# Encoders.net
KiCad netlist of a schematic drawn in Altium Designer
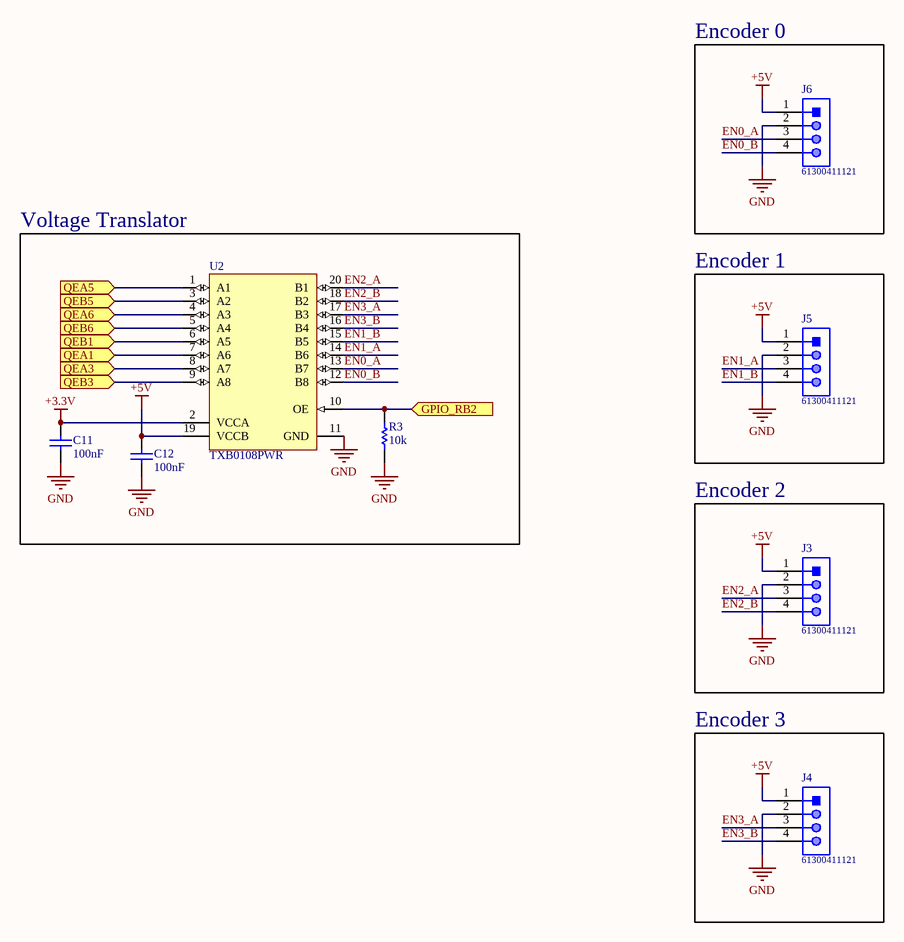
[diagram p0: Encoders.SchDoc]

(export (version "E")
  (design (tool "Eeschema 10.0.6"))
  (components
    (comp (ref "C11")
      (value "100nF")
      (footprint "0402")
      (description "TDK - C1005X7R1C104K050BC. - CERAMIC CAPACITOR, 0.1UF, 16V, X7R, 10%, 0402, FULL REEL")
      (fields
        (field (name "MANUFACTURER") "TDK")
        (field (name "MANUFACTURER PART NUMBER") "C1005X7R1C104K050BC")
      )
      (libsource (lib "altium-library") (part "Capacitor"))
    )
    (comp (ref "C12")
      (value "100nF")
      (footprint "0402")
      (description "TDK - C1005X7R1C104K050BC. - CERAMIC CAPACITOR, 0.1UF, 16V, X7R, 10%, 0402, FULL REEL")
      (fields
        (field (name "MANUFACTURER") "TDK")
        (field (name "MANUFACTURER PART NUMBER") "C1005X7R1C104K050BC")
      )
      (libsource (lib "altium-library") (part "Capacitor"))
    )
    (comp (ref "J3")
      (value "61300411121")
      (footprint "61300411121")
      (description "THT Vertical Pin Header WR-PHD, Pitch 2.54 mm, Single Row, 4 pins")
      (fields (field (name "MANUFACTURER") "Wurth Elektronik") (field (name "PUBLISHER") "WurthElektronik"))
      (libsource (lib "Altium Content Vault") (part "WE-CN-1P-M-R4"))
    )
    (comp (ref "J4")
      (value "61300411121")
      (footprint "61300411121")
      (description "THT Vertical Pin Header WR-PHD, Pitch 2.54 mm, Single Row, 4 pins")
      (fields (field (name "MANUFACTURER") "Wurth Elektronik") (field (name "PUBLISHER") "WurthElektronik"))
      (libsource (lib "Altium Content Vault") (part "WE-CN-1P-M-R4"))
    )
    (comp (ref "J5")
      (value "61300411121")
      (footprint "61300411121")
      (description "THT Vertical Pin Header WR-PHD, Pitch 2.54 mm, Single Row, 4 pins")
      (fields (field (name "MANUFACTURER") "Wurth Elektronik") (field (name "PUBLISHER") "WurthElektronik"))
      (libsource (lib "Altium Content Vault") (part "WE-CN-1P-M-R4"))
    )
    (comp (ref "J6")
      (value "61300411121")
      (footprint "61300411121")
      (description "THT Vertical Pin Header WR-PHD, Pitch 2.54 mm, Single Row, 4 pins")
      (fields (field (name "MANUFACTURER") "Wurth Elektronik") (field (name "PUBLISHER") "WurthElektronik"))
      (libsource (lib "Altium Content Vault") (part "WE-CN-1P-M-R4"))
    )
    (comp (ref "R3")
      (value "10k")
      (footprint "0402")
      (description "D10/CRCW0402-C 100 10K 1% ET7")
      (fields
        (field (name "MANUFACTURER") "Vishay")
        (field (name "MANUFACTURER PART NUMBER") "CRCW040210K0FKEDC")
      )
      (libsource (lib "altium-library") (part "Resistor"))
    )
    (comp (ref "U2")
      (value "TXB0108PWR")
      (footprint "PW0020A_L")
      (fields (field (name "MANUFACTURER") "Texas Instruments"))
      (libsource (lib "Altium Content Vault") (part "TI-TXB0108-PW-20"))
    )
  )
  (nets
    (net (code "1") (name "+3.3V") (class "Default")
      (node (ref "C11") (pin "2") (pinfunction "2_2") (pintype "passive"))
      (node (ref "U2") (pin "2") (pinfunction "VCCA_2") (pintype "power_in"))
    )
    (net (code "2") (name "+5V") (class "Default")
      (node (ref "C12") (pin "2") (pinfunction "2_2") (pintype "passive"))
      (node (ref "J3") (pin "1") (pinfunction "1_1") (pintype "passive"))
      (node (ref "J4") (pin "1") (pinfunction "1_1") (pintype "passive"))
      (node (ref "J5") (pin "1") (pinfunction "1_1") (pintype "passive"))
      (node (ref "J6") (pin "1") (pinfunction "1_1") (pintype "passive"))
      (node (ref "U2") (pin "19") (pinfunction "VCCB_19") (pintype "power_in"))
    )
    (net (code "3") (name "/EN0_A") (class "Default")
      (node (ref "J6") (pin "3") (pinfunction "3_3") (pintype "passive"))
      (node (ref "U2") (pin "13") (pinfunction "B7_13") (pintype "bidirectional"))
    )
    (net (code "4") (name "/EN0_B") (class "Default")
      (node (ref "J6") (pin "4") (pinfunction "4_4") (pintype "passive"))
      (node (ref "U2") (pin "12") (pinfunction "B8_12") (pintype "bidirectional"))
    )
    (net (code "5") (name "/EN1_A") (class "Default")
      (node (ref "J5") (pin "3") (pinfunction "3_3") (pintype "passive"))
      (node (ref "U2") (pin "14") (pinfunction "B6_14") (pintype "bidirectional"))
    )
    (net (code "6") (name "/EN1_B") (class "Default")
      (node (ref "J5") (pin "4") (pinfunction "4_4") (pintype "passive"))
      (node (ref "U2") (pin "15") (pinfunction "B5_15") (pintype "bidirectional"))
    )
    (net (code "7") (name "/EN2_A") (class "Default")
      (node (ref "J3") (pin "3") (pinfunction "3_3") (pintype "passive"))
      (node (ref "U2") (pin "20") (pinfunction "B1_20") (pintype "bidirectional"))
    )
    (net (code "8") (name "/EN2_B") (class "Default")
      (node (ref "J3") (pin "4") (pinfunction "4_4") (pintype "passive"))
      (node (ref "U2") (pin "18") (pinfunction "B2_18") (pintype "bidirectional"))
    )
    (net (code "9") (name "/EN3_A") (class "Default")
      (node (ref "J4") (pin "3") (pinfunction "3_3") (pintype "passive"))
      (node (ref "U2") (pin "17") (pinfunction "B3_17") (pintype "bidirectional"))
    )
    (net (code "10") (name "/EN3_B") (class "Default")
      (node (ref "J4") (pin "4") (pinfunction "4_4") (pintype "passive"))
      (node (ref "U2") (pin "16") (pinfunction "B4_16") (pintype "bidirectional"))
    )
    (net (code "11") (name "/GPIO_RB2") (class "Default")
      (node (ref "R3") (pin "2") (pinfunction "2_2") (pintype "passive"))
      (node (ref "U2") (pin "10") (pinfunction "OE_10") (pintype "input"))
    )
    (net (code "12") (name "/QEA1") (class "Default")
      (node (ref "U2") (pin "7") (pinfunction "A6_7") (pintype "bidirectional"))
    )
    (net (code "13") (name "/QEA3") (class "Default")
      (node (ref "U2") (pin "8") (pinfunction "A7_8") (pintype "bidirectional"))
    )
    (net (code "14") (name "/QEA5") (class "Default")
      (node (ref "U2") (pin "1") (pinfunction "A1_1") (pintype "bidirectional"))
    )
    (net (code "15") (name "/QEA6") (class "Default")
      (node (ref "U2") (pin "4") (pinfunction "A3_4") (pintype "bidirectional"))
    )
    (net (code "16") (name "/QEB1") (class "Default")
      (node (ref "U2") (pin "6") (pinfunction "A5_6") (pintype "bidirectional"))
    )
    (net (code "17") (name "/QEB3") (class "Default")
      (node (ref "U2") (pin "9") (pinfunction "A8_9") (pintype "bidirectional"))
    )
    (net (code "18") (name "/QEB5") (class "Default")
      (node (ref "U2") (pin "3") (pinfunction "A2_3") (pintype "bidirectional"))
    )
    (net (code "19") (name "/QEB6") (class "Default")
      (node (ref "U2") (pin "5") (pinfunction "A4_5") (pintype "bidirectional"))
    )
    (net (code "20") (name "GND") (class "Default")
      (node (ref "C11") (pin "1") (pinfunction "1_1") (pintype "passive"))
      (node (ref "C12") (pin "1") (pinfunction "1_1") (pintype "passive"))
      (node (ref "J3") (pin "2") (pinfunction "2_2") (pintype "passive"))
      (node (ref "J4") (pin "2") (pinfunction "2_2") (pintype "passive"))
      (node (ref "J5") (pin "2") (pinfunction "2_2") (pintype "passive"))
      (node (ref "J6") (pin "2") (pinfunction "2_2") (pintype "passive"))
      (node (ref "R3") (pin "1") (pinfunction "1_1") (pintype "passive"))
      (node (ref "U2") (pin "11") (pinfunction "GND_11") (pintype "power_in"))
    )
  )
)
